# SCH_Design.net
KiCad netlist of a schematic drawn in EasyEDA
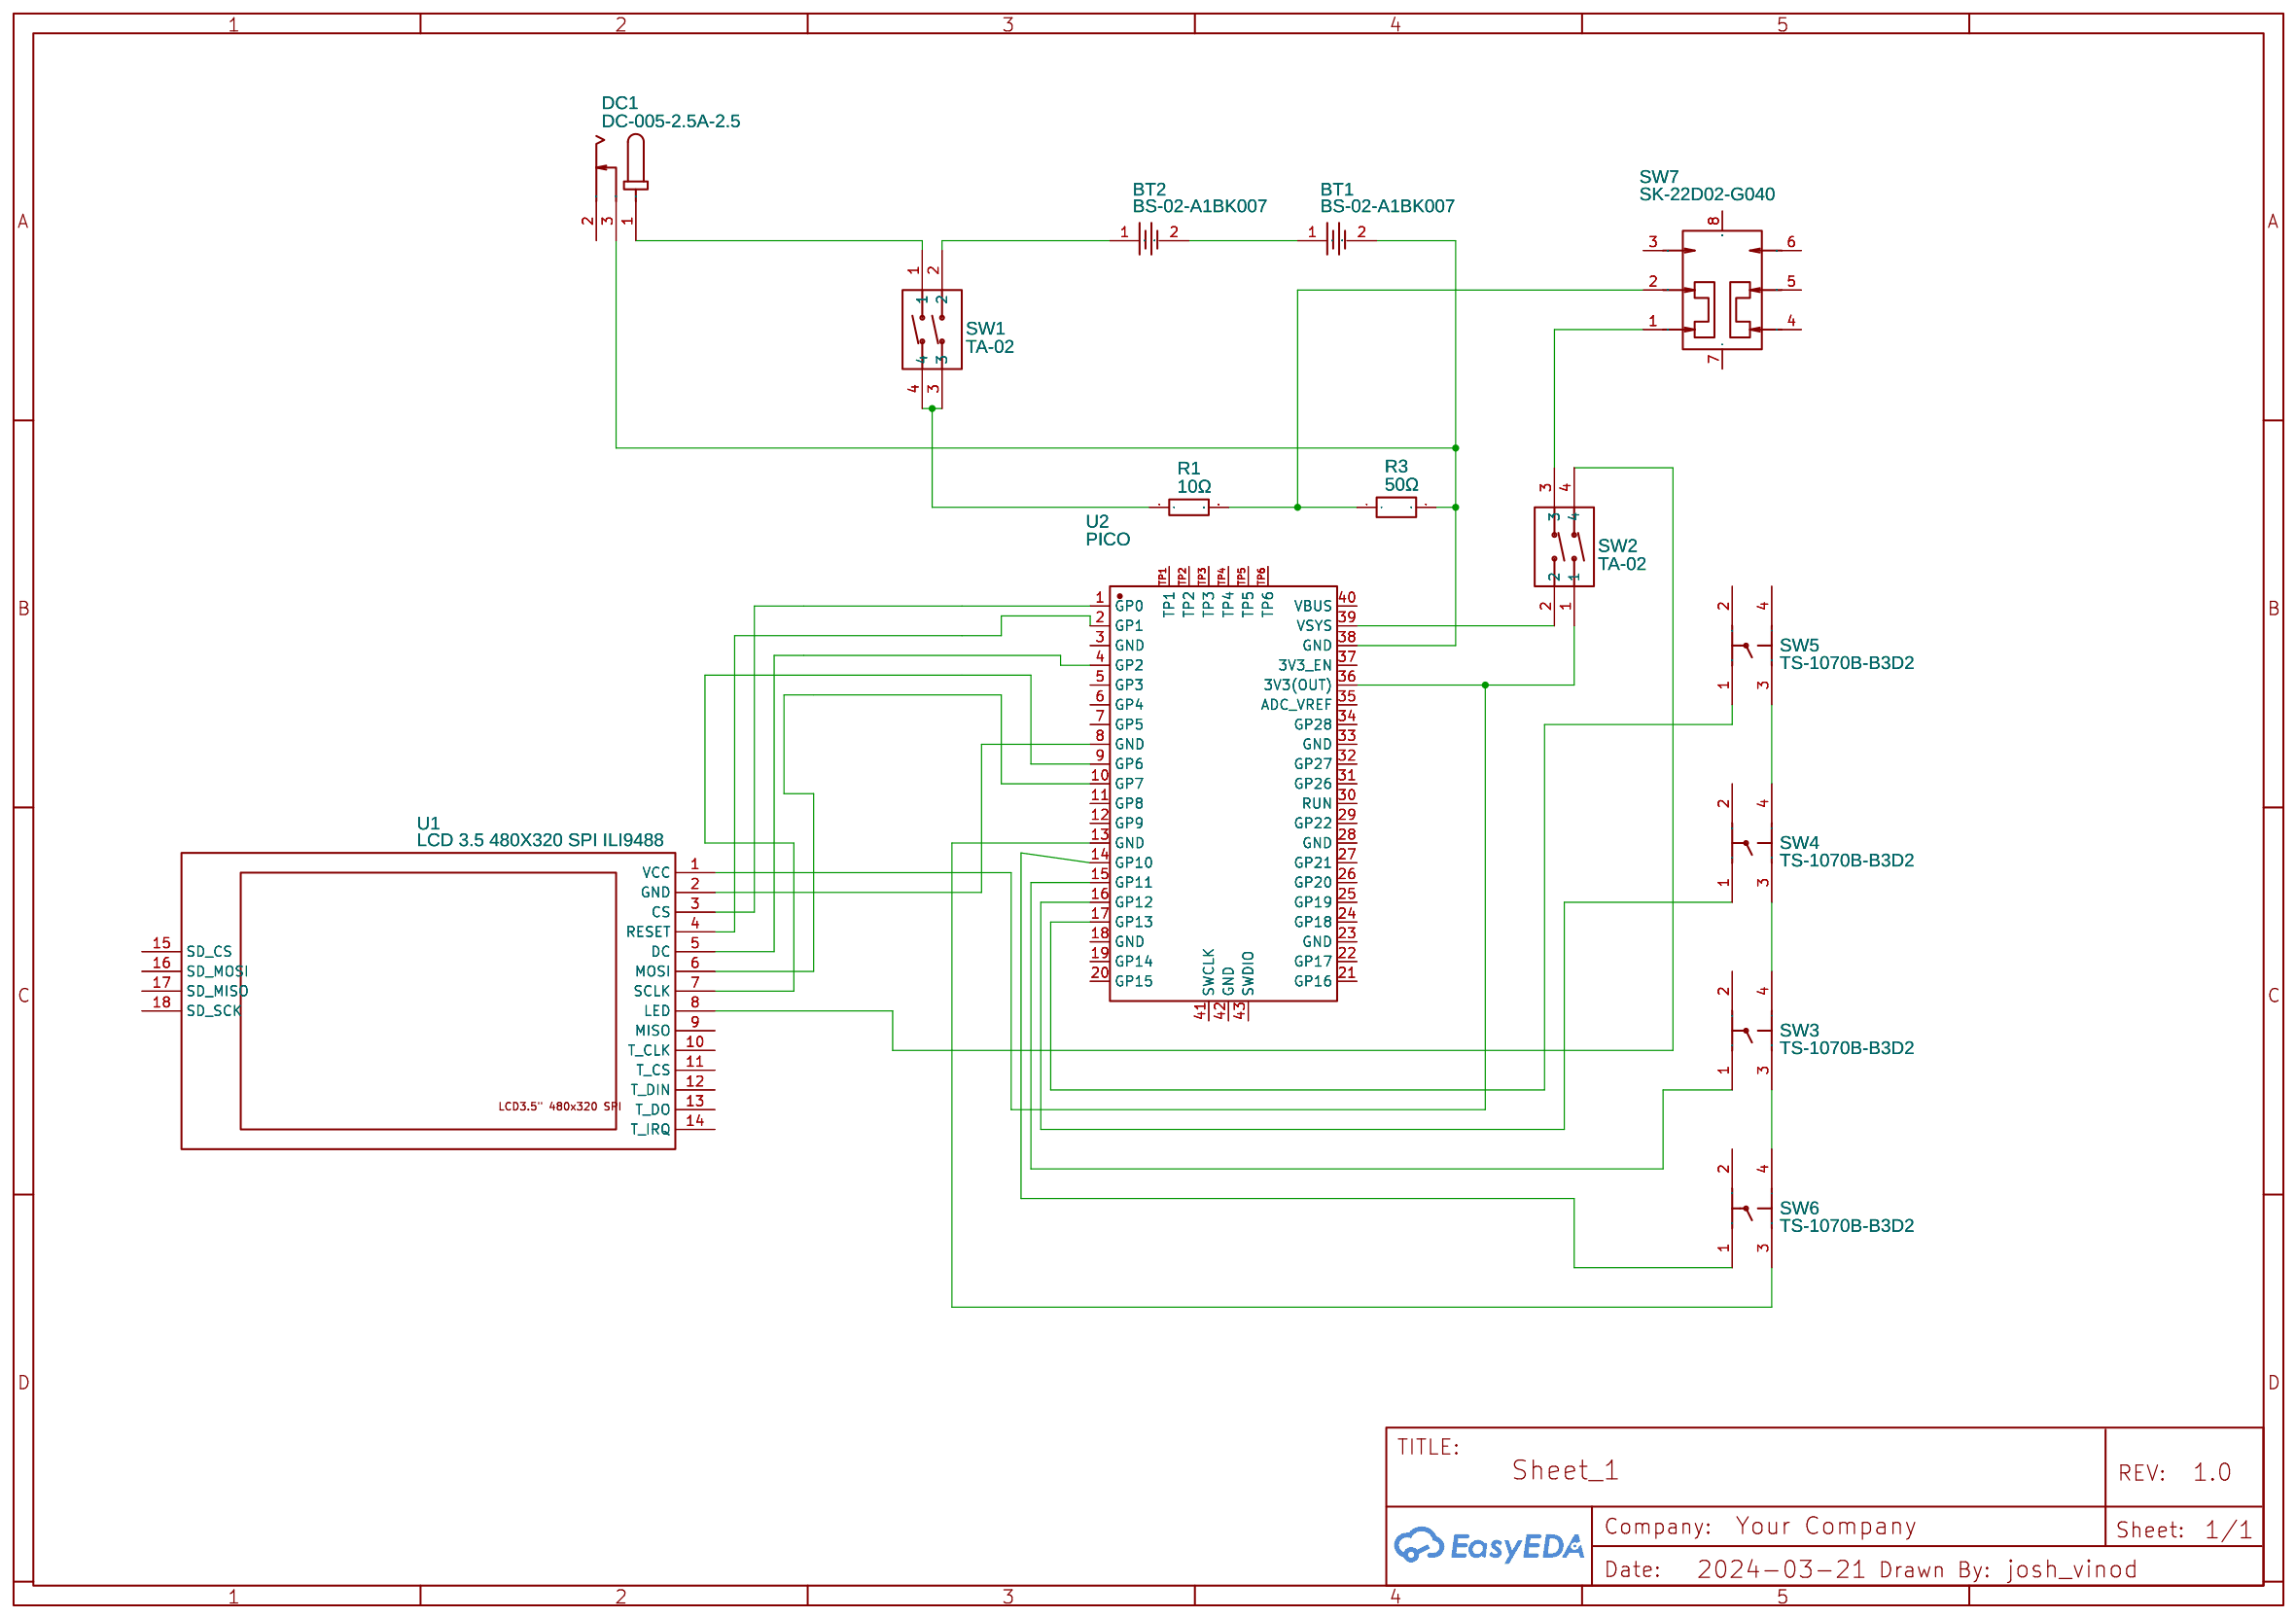
[diagram p0: schematic sheet]

(export (version "E")
  (design (tool "Eeschema 10.0.6"))
  (components
    (comp (ref "BT1")
      (value "BS-02-A1BK007")
      (fields (field (name "Manufacturer") "MYOUNG(美阳)"))
      (libsource (lib "") (part "BS-02-A1BK007"))
    )
    (comp (ref "BT2")
      (value "BS-02-A1BK007")
      (fields (field (name "Manufacturer") "MYOUNG(美阳)"))
      (libsource (lib "") (part "BS-02-A1BK007"))
    )
    (comp (ref "DC1")
      (value "DC-005-2.5A-2.5")
      (fields (field (name "Manufacturer") "XKB Enterprise"))
      (libsource (lib "") (part "DC-005-2.5A-2.5"))
    )
    (comp (ref "R1")
      (value "10Ω")
      (fields
        (field (name "Manufacturer Part") "0603WAF100JT5E")
        (field (name "Manufacturer") "UNI-ROYAL(厚声)")
      )
      (libsource (lib "") (part "0603WAF100JT5E"))
    )
    (comp (ref "R3")
      (value "50Ω")
      (fields (field (name "Manufacturer Part") "ARG05FTC0500") (field (name "Manufacturer") "Viking(光颉)"))
      (libsource (lib "") (part "ARG05FTC0500"))
    )
    (comp (ref "SW1")
      (value "TA-02")
      (fields (field (name "Manufacturer") "Yuandi(元迪)"))
      (libsource (lib "") (part "TA-02"))
    )
    (comp (ref "SW2")
      (value "TA-02")
      (fields (field (name "Manufacturer") "Yuandi(元迪)"))
      (libsource (lib "") (part "TA-02_1"))
    )
    (comp (ref "SW3")
      (value "TS-1070B-B3D2")
      (fields (field (name "Manufacturer") "Yuandi(元迪)"))
      (libsource (lib "") (part "TS-1070B-B3D2"))
    )
    (comp (ref "SW4")
      (value "TS-1070B-B3D2")
      (fields (field (name "Manufacturer") "Yuandi(元迪)"))
      (libsource (lib "") (part "TS-1070B-B3D2"))
    )
    (comp (ref "SW5")
      (value "TS-1070B-B3D2")
      (fields (field (name "Manufacturer") "Yuandi(元迪)"))
      (libsource (lib "") (part "TS-1070B-B3D2"))
    )
    (comp (ref "SW6")
      (value "TS-1070B-B3D2")
      (fields (field (name "Manufacturer") "Yuandi(元迪)"))
      (libsource (lib "") (part "TS-1070B-B3D2"))
    )
    (comp (ref "SW7")
      (value "SK-22D02-G040")
      (fields (field (name "Manufacturer") "G-Switch(品赞)"))
      (libsource (lib "") (part "SK-22D02-G040"))
    )
    (comp (ref "U1")
      (value "LCD 3.5 480X320 SPI ILI9488")
      (libsource (lib "") (part "LCD 3.5 480X320 SPI ILI9488"))
    )
    (comp (ref "U2")
      (value "PICO")
      (fields (field (name "Manufacturer") "Raspberry Pi(树莓派)"))
      (libsource (lib "") (part "PICO"))
    )
  )
  (nets
    (net (code "1") (name "Net-(BT1-Pad1)") (class "Default")
      (node (ref "BT1") (pin "1") (pinfunction "1_1") (pintype "input"))
      (node (ref "BT2") (pin "2") (pinfunction "2_2") (pintype "input"))
    )
    (net (code "2") (name "Net-(BT1-Pad2)") (class "Default")
      (node (ref "BT1") (pin "2") (pinfunction "2_2") (pintype "input"))
      (node (ref "DC1") (pin "3") (pinfunction "3_3") (pintype "unspecified"))
      (node (ref "R3") (pin "2") (pinfunction "2_2") (pintype "unspecified"))
      (node (ref "U2") (pin "38") (pinfunction "GND_38") (pintype "unspecified"))
    )
    (net (code "3") (name "Net-(BT2-Pad1)") (class "Default")
      (node (ref "BT2") (pin "1") (pinfunction "1_1") (pintype "input"))
      (node (ref "SW1") (pin "2") (pinfunction "2_2") (pintype "unspecified"))
    )
    (net (code "4") (name "Net-(DC1-Pad1)") (class "Default")
      (node (ref "DC1") (pin "1") (pinfunction "1_1") (pintype "unspecified"))
      (node (ref "SW1") (pin "1") (pinfunction "1_1") (pintype "unspecified"))
    )
    (net (code "5") (name "Net-(R1-Pad1)") (class "Default")
      (node (ref "R1") (pin "1") (pinfunction "1_1") (pintype "input"))
      (node (ref "SW1") (pin "3") (pinfunction "3_3") (pintype "unspecified"))
      (node (ref "SW1") (pin "4") (pinfunction "4_4") (pintype "unspecified"))
    )
    (net (code "6") (name "Net-(R1-Pad2)") (class "Default")
      (node (ref "R1") (pin "2") (pinfunction "2_2") (pintype "input"))
      (node (ref "R3") (pin "1") (pinfunction "1_1") (pintype "unspecified"))
      (node (ref "SW7") (pin "2") (pinfunction "2_2") (pintype "unspecified"))
    )
    (net (code "7") (name "Net-(SW2-Pad3)") (class "Default")
      (node (ref "SW2") (pin "3") (pinfunction "3_3") (pintype "unspecified"))
      (node (ref "SW7") (pin "1") (pinfunction "1_1") (pintype "unspecified"))
    )
    (net (code "8") (name "Net-(SW3-Pad3)") (class "Default")
      (node (ref "SW3") (pin "3") (pinfunction "3_3") (pintype "unspecified"))
      (node (ref "SW6") (pin "4") (pinfunction "4_4") (pintype "unspecified"))
    )
    (net (code "9") (name "Net-(SW3-Pad4)") (class "Default")
      (node (ref "SW3") (pin "4") (pinfunction "4_4") (pintype "unspecified"))
      (node (ref "SW4") (pin "3") (pinfunction "3_3") (pintype "unspecified"))
    )
    (net (code "10") (name "Net-(SW4-Pad4)") (class "Default")
      (node (ref "SW4") (pin "4") (pinfunction "4_4") (pintype "unspecified"))
      (node (ref "SW5") (pin "3") (pinfunction "3_3") (pintype "unspecified"))
    )
    (net (code "11") (name "Net-(SW6-Pad3)") (class "Default")
      (node (ref "SW6") (pin "3") (pinfunction "3_3") (pintype "unspecified"))
      (node (ref "U2") (pin "13") (pinfunction "GND_13") (pintype "unspecified"))
    )
    (net (code "12") (name "Net-(U1-CS)") (class "Default")
      (node (ref "U1") (pin "3") (pinfunction "CS_3") (pintype "input"))
      (node (ref "U2") (pin "1") (pinfunction "GP0_1") (pintype "unspecified"))
    )
    (net (code "13") (name "Net-(U1-DC)") (class "Default")
      (node (ref "U1") (pin "5") (pinfunction "DC_5") (pintype "input"))
      (node (ref "U2") (pin "4") (pinfunction "GP2_4") (pintype "unspecified"))
    )
    (net (code "14") (name "Net-(U1-GND)") (class "Default")
      (node (ref "U1") (pin "2") (pinfunction "GND_2") (pintype "passive"))
      (node (ref "U2") (pin "8") (pinfunction "GND_8") (pintype "unspecified"))
    )
    (net (code "15") (name "Net-(U1-LED)") (class "Default")
      (node (ref "SW2") (pin "4") (pinfunction "4_4") (pintype "unspecified"))
      (node (ref "U1") (pin "8") (pinfunction "LED_8") (pintype "passive"))
    )
    (net (code "16") (name "Net-(U1-MOSI)") (class "Default")
      (node (ref "U1") (pin "6") (pinfunction "MOSI_6") (pintype "input"))
      (node (ref "U2") (pin "10") (pinfunction "GP7_10") (pintype "unspecified"))
    )
    (net (code "17") (name "Net-(U1-RESET)") (class "Default")
      (node (ref "U1") (pin "4") (pinfunction "RESET_4") (pintype "input"))
      (node (ref "U2") (pin "2") (pinfunction "GP1_2") (pintype "unspecified"))
    )
    (net (code "18") (name "Net-(U1-SCLK)") (class "Default")
      (node (ref "U1") (pin "7") (pinfunction "SCLK_7") (pintype "input"))
      (node (ref "U2") (pin "9") (pinfunction "GP6_9") (pintype "unspecified"))
    )
    (net (code "19") (name "Net-(U1-VCC)") (class "Default")
      (node (ref "SW2") (pin "1") (pinfunction "1_1") (pintype "unspecified"))
      (node (ref "U1") (pin "1") (pinfunction "VCC_1") (pintype "passive"))
      (node (ref "U2") (pin "36") (pinfunction "3V3(OUT)_36") (pintype "unspecified"))
    )
    (net (code "20") (name "Net-(U2-GP10)") (class "Default")
      (node (ref "SW6") (pin "1") (pinfunction "1_1") (pintype "unspecified"))
      (node (ref "U2") (pin "14") (pinfunction "GP10_14") (pintype "unspecified"))
    )
    (net (code "21") (name "Net-(U2-GP11)") (class "Default")
      (node (ref "SW3") (pin "1") (pinfunction "1_1") (pintype "unspecified"))
      (node (ref "U2") (pin "15") (pinfunction "GP11_15") (pintype "unspecified"))
    )
    (net (code "22") (name "Net-(U2-GP12)") (class "Default")
      (node (ref "SW4") (pin "1") (pinfunction "1_1") (pintype "unspecified"))
      (node (ref "U2") (pin "16") (pinfunction "GP12_16") (pintype "unspecified"))
    )
    (net (code "23") (name "Net-(U2-GP13)") (class "Default")
      (node (ref "SW5") (pin "1") (pinfunction "1_1") (pintype "unspecified"))
      (node (ref "U2") (pin "17") (pinfunction "GP13_17") (pintype "unspecified"))
    )
    (net (code "24") (name "Net-(U2-VSYS)") (class "Default")
      (node (ref "SW2") (pin "2") (pinfunction "2_2") (pintype "unspecified"))
      (node (ref "U2") (pin "39") (pinfunction "VSYS_39") (pintype "unspecified"))
    )
    (net (code "25") (name "unconnected-(DC1-Pad2)") (class "Default")
      (node (ref "DC1") (pin "2") (pinfunction "2_2") (pintype "unspecified"))
    )
    (net (code "26") (name "unconnected-(SW3-Pad2)") (class "Default")
      (node (ref "SW3") (pin "2") (pinfunction "2_2") (pintype "unspecified"))
    )
    (net (code "27") (name "unconnected-(SW4-Pad2)") (class "Default")
      (node (ref "SW4") (pin "2") (pinfunction "2_2") (pintype "unspecified"))
    )
    (net (code "28") (name "unconnected-(SW5-Pad2)") (class "Default")
      (node (ref "SW5") (pin "2") (pinfunction "2_2") (pintype "unspecified"))
    )
    (net (code "29") (name "unconnected-(SW5-Pad4)") (class "Default")
      (node (ref "SW5") (pin "4") (pinfunction "4_4") (pintype "unspecified"))
    )
    (net (code "30") (name "unconnected-(SW6-Pad2)") (class "Default")
      (node (ref "SW6") (pin "2") (pinfunction "2_2") (pintype "unspecified"))
    )
    (net (code "31") (name "unconnected-(SW7-Pad3)") (class "Default")
      (node (ref "SW7") (pin "3") (pinfunction "3_3") (pintype "unspecified"))
    )
    (net (code "32") (name "unconnected-(SW7-Pad4)") (class "Default")
      (node (ref "SW7") (pin "4") (pinfunction "4_4") (pintype "unspecified"))
    )
    (net (code "33") (name "unconnected-(SW7-Pad5)") (class "Default")
      (node (ref "SW7") (pin "5") (pinfunction "5_5") (pintype "unspecified"))
    )
    (net (code "34") (name "unconnected-(SW7-Pad6)") (class "Default")
      (node (ref "SW7") (pin "6") (pinfunction "6_6") (pintype "unspecified"))
    )
    (net (code "35") (name "unconnected-(SW7-Pad7)") (class "Default")
      (node (ref "SW7") (pin "7") (pinfunction "7_7") (pintype "unspecified"))
    )
    (net (code "36") (name "unconnected-(SW7-Pad8)") (class "Default")
      (node (ref "SW7") (pin "8") (pinfunction "8_8") (pintype "unspecified"))
    )
    (net (code "37") (name "unconnected-(U1-MISO-Pad9)") (class "Default")
      (node (ref "U1") (pin "9") (pinfunction "MISO_9") (pintype "output"))
    )
    (net (code "38") (name "unconnected-(U1-SD_CS-Pad15)") (class "Default")
      (node (ref "U1") (pin "15") (pinfunction "SD_CS_15") (pintype "passive"))
    )
    (net (code "39") (name "unconnected-(U1-SD_MISO-Pad17)") (class "Default")
      (node (ref "U1") (pin "17") (pinfunction "SD_MISO_17") (pintype "passive"))
    )
    (net (code "40") (name "unconnected-(U1-SD_MOSI-Pad16)") (class "Default")
      (node (ref "U1") (pin "16") (pinfunction "SD_MOSI_16") (pintype "passive"))
    )
    (net (code "41") (name "unconnected-(U1-SD_SCK-Pad18)") (class "Default")
      (node (ref "U1") (pin "18") (pinfunction "SD_SCK_18") (pintype "passive"))
    )
    (net (code "42") (name "unconnected-(U1-T_CLK-Pad10)") (class "Default")
      (node (ref "U1") (pin "10") (pinfunction "T_CLK_10") (pintype "unspecified"))
    )
    (net (code "43") (name "unconnected-(U1-T_CS-Pad11)") (class "Default")
      (node (ref "U1") (pin "11") (pinfunction "T_CS_11") (pintype "unspecified"))
    )
    (net (code "44") (name "unconnected-(U1-T_DIN-Pad12)") (class "Default")
      (node (ref "U1") (pin "12") (pinfunction "T_DIN_12") (pintype "unspecified"))
    )
    (net (code "45") (name "unconnected-(U1-T_DO-Pad13)") (class "Default")
      (node (ref "U1") (pin "13") (pinfunction "T_DO_13") (pintype "unspecified"))
    )
    (net (code "46") (name "unconnected-(U1-T_IRQ-Pad14)") (class "Default")
      (node (ref "U1") (pin "14") (pinfunction "T_IRQ_14") (pintype "unspecified"))
    )
    (net (code "47") (name "unconnected-(U2-3V3_EN-Pad37)") (class "Default")
      (node (ref "U2") (pin "37") (pinfunction "3V3_EN_37") (pintype "unspecified"))
    )
    (net (code "48") (name "unconnected-(U2-ADC_VREF-Pad35)") (class "Default")
      (node (ref "U2") (pin "35") (pinfunction "ADC_VREF_35") (pintype "unspecified"))
    )
    (net (code "49") (name "unconnected-(U2-GND-Pad3)") (class "Default")
      (node (ref "U2") (pin "3") (pinfunction "GND_3") (pintype "unspecified"))
    )
    (net (code "50") (name "unconnected-(U2-GND-Pad18)") (class "Default")
      (node (ref "U2") (pin "18") (pinfunction "GND_18") (pintype "unspecified"))
    )
    (net (code "51") (name "unconnected-(U2-GND-Pad23)") (class "Default")
      (node (ref "U2") (pin "23") (pinfunction "GND_23") (pintype "unspecified"))
    )
    (net (code "52") (name "unconnected-(U2-GND-Pad28)") (class "Default")
      (node (ref "U2") (pin "28") (pinfunction "GND_28") (pintype "unspecified"))
    )
    (net (code "53") (name "unconnected-(U2-GND-Pad33)") (class "Default")
      (node (ref "U2") (pin "33") (pinfunction "GND_33") (pintype "unspecified"))
    )
    (net (code "54") (name "unconnected-(U2-GND-Pad42)") (class "Default")
      (node (ref "U2") (pin "42") (pinfunction "GND_42") (pintype "unspecified"))
    )
    (net (code "55") (name "unconnected-(U2-GP3-Pad5)") (class "Default")
      (node (ref "U2") (pin "5") (pinfunction "GP3_5") (pintype "unspecified"))
    )
    (net (code "56") (name "unconnected-(U2-GP4-Pad6)") (class "Default")
      (node (ref "U2") (pin "6") (pinfunction "GP4_6") (pintype "unspecified"))
    )
    (net (code "57") (name "unconnected-(U2-GP5-Pad7)") (class "Default")
      (node (ref "U2") (pin "7") (pinfunction "GP5_7") (pintype "unspecified"))
    )
    (net (code "58") (name "unconnected-(U2-GP8-Pad11)") (class "Default")
      (node (ref "U2") (pin "11") (pinfunction "GP8_11") (pintype "unspecified"))
    )
    (net (code "59") (name "unconnected-(U2-GP9-Pad12)") (class "Default")
      (node (ref "U2") (pin "12") (pinfunction "GP9_12") (pintype "unspecified"))
    )
    (net (code "60") (name "unconnected-(U2-GP14-Pad19)") (class "Default")
      (node (ref "U2") (pin "19") (pinfunction "GP14_19") (pintype "unspecified"))
    )
    (net (code "61") (name "unconnected-(U2-GP15-Pad20)") (class "Default")
      (node (ref "U2") (pin "20") (pinfunction "GP15_20") (pintype "unspecified"))
    )
    (net (code "62") (name "unconnected-(U2-GP16-Pad21)") (class "Default")
      (node (ref "U2") (pin "21") (pinfunction "GP16_21") (pintype "unspecified"))
    )
    (net (code "63") (name "unconnected-(U2-GP17-Pad22)") (class "Default")
      (node (ref "U2") (pin "22") (pinfunction "GP17_22") (pintype "unspecified"))
    )
    (net (code "64") (name "unconnected-(U2-GP18-Pad24)") (class "Default")
      (node (ref "U2") (pin "24") (pinfunction "GP18_24") (pintype "unspecified"))
    )
    (net (code "65") (name "unconnected-(U2-GP19-Pad25)") (class "Default")
      (node (ref "U2") (pin "25") (pinfunction "GP19_25") (pintype "unspecified"))
    )
    (net (code "66") (name "unconnected-(U2-GP20-Pad26)") (class "Default")
      (node (ref "U2") (pin "26") (pinfunction "GP20_26") (pintype "unspecified"))
    )
    (net (code "67") (name "unconnected-(U2-GP21-Pad27)") (class "Default")
      (node (ref "U2") (pin "27") (pinfunction "GP21_27") (pintype "unspecified"))
    )
    (net (code "68") (name "unconnected-(U2-GP22-Pad29)") (class "Default")
      (node (ref "U2") (pin "29") (pinfunction "GP22_29") (pintype "unspecified"))
    )
    (net (code "69") (name "unconnected-(U2-GP26-Pad31)") (class "Default")
      (node (ref "U2") (pin "31") (pinfunction "GP26_31") (pintype "unspecified"))
    )
    (net (code "70") (name "unconnected-(U2-GP27-Pad32)") (class "Default")
      (node (ref "U2") (pin "32") (pinfunction "GP27_32") (pintype "unspecified"))
    )
    (net (code "71") (name "unconnected-(U2-GP28-Pad34)") (class "Default")
      (node (ref "U2") (pin "34") (pinfunction "GP28_34") (pintype "unspecified"))
    )
    (net (code "72") (name "unconnected-(U2-PadTP1)") (class "Default")
      (node (ref "U2") (pin "TP1") (pinfunction "TP1_TP1") (pintype "unspecified"))
    )
    (net (code "73") (name "unconnected-(U2-PadTP2)") (class "Default")
      (node (ref "U2") (pin "TP2") (pinfunction "TP2_TP2") (pintype "unspecified"))
    )
    (net (code "74") (name "unconnected-(U2-PadTP3)") (class "Default")
      (node (ref "U2") (pin "TP3") (pinfunction "TP3_TP3") (pintype "unspecified"))
    )
    (net (code "75") (name "unconnected-(U2-PadTP4)") (class "Default")
      (node (ref "U2") (pin "TP4") (pinfunction "TP4_TP4") (pintype "unspecified"))
    )
    (net (code "76") (name "unconnected-(U2-PadTP5)") (class "Default")
      (node (ref "U2") (pin "TP5") (pinfunction "TP5_TP5") (pintype "unspecified"))
    )
    (net (code "77") (name "unconnected-(U2-PadTP6)") (class "Default")
      (node (ref "U2") (pin "TP6") (pinfunction "TP6_TP6") (pintype "unspecified"))
    )
    (net (code "78") (name "unconnected-(U2-RUN-Pad30)") (class "Default")
      (node (ref "U2") (pin "30") (pinfunction "RUN_30") (pintype "unspecified"))
    )
    (net (code "79") (name "unconnected-(U2-SWCLK-Pad41)") (class "Default")
      (node (ref "U2") (pin "41") (pinfunction "SWCLK_41") (pintype "unspecified"))
    )
    (net (code "80") (name "unconnected-(U2-SWDIO-Pad43)") (class "Default")
      (node (ref "U2") (pin "43") (pinfunction "SWDIO_43") (pintype "unspecified"))
    )
    (net (code "81") (name "unconnected-(U2-VBUS-Pad40)") (class "Default")
      (node (ref "U2") (pin "40") (pinfunction "VBUS_40") (pintype "unspecified"))
    )
  )
)
